# mcu.net
KiCad netlist of a schematic drawn in EAGLE
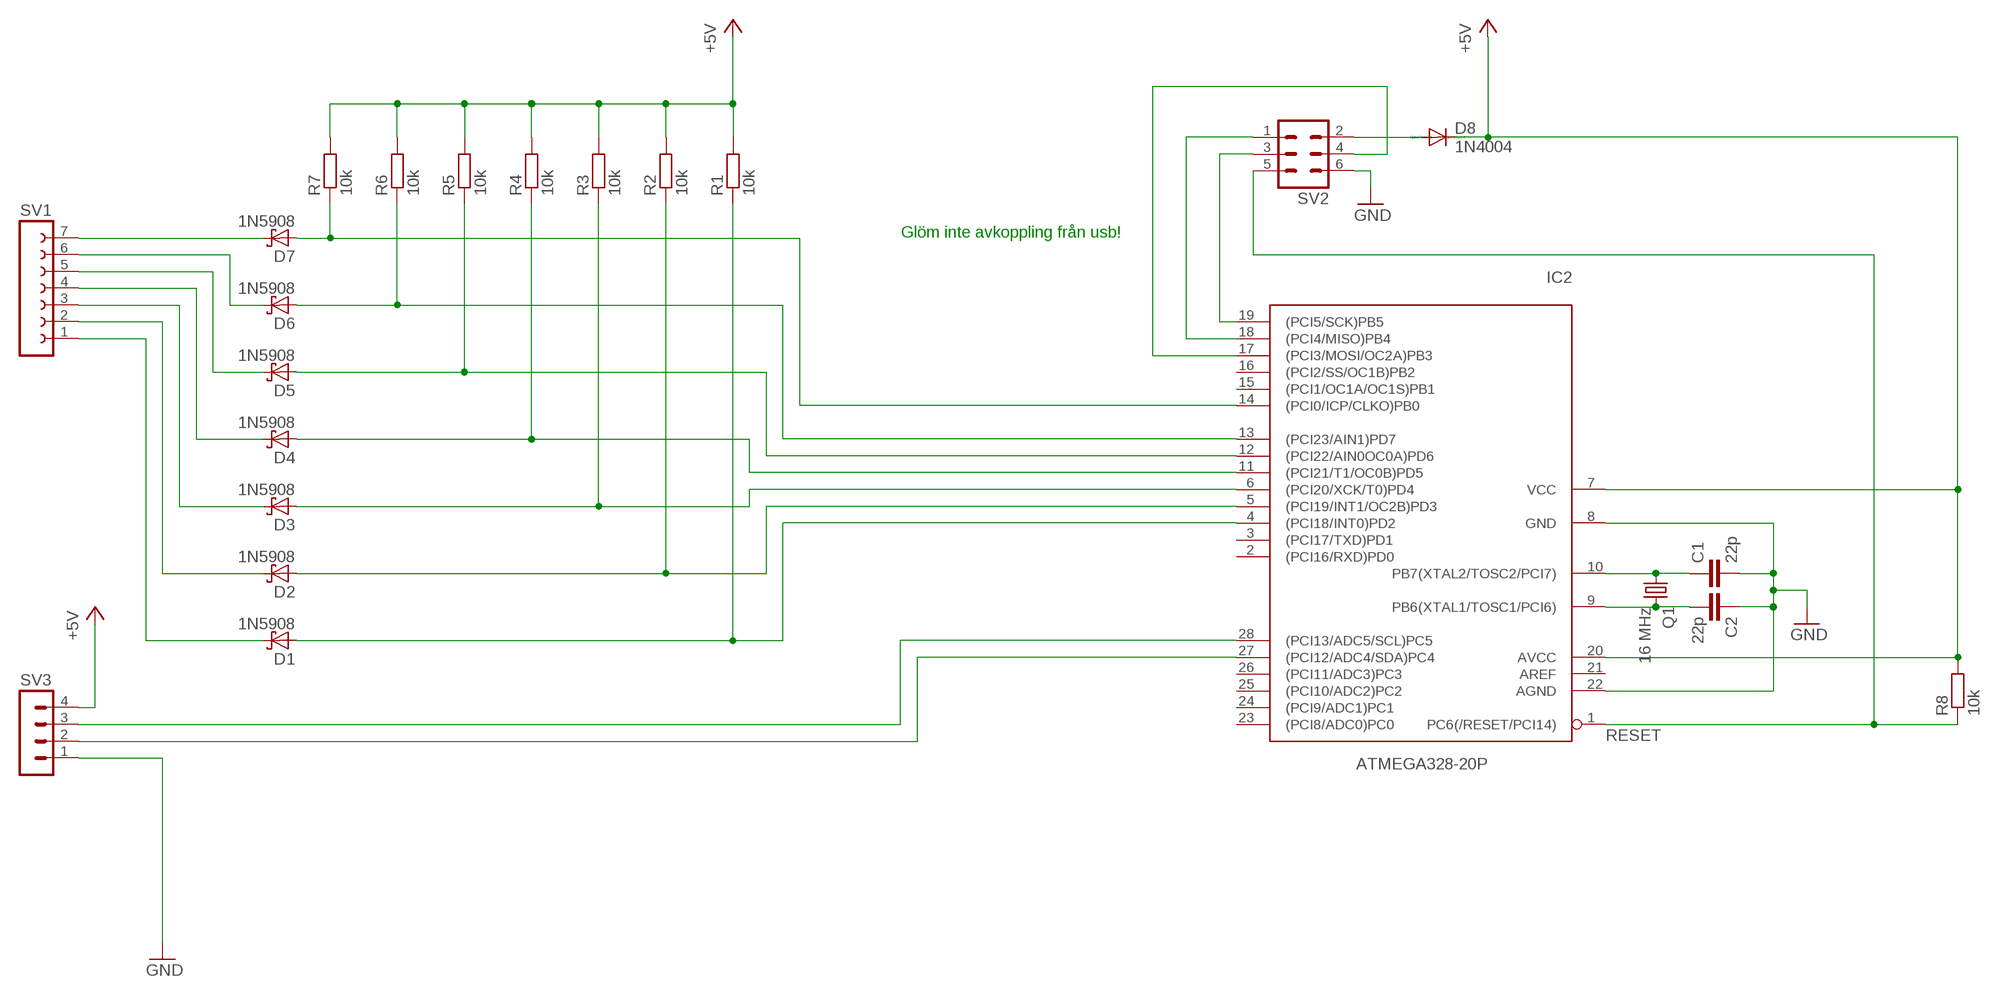
[diagram p0: schematic, sheet 1]

(export (version "E")
  (design (tool "Eeschema 10.0.6"))
  (components
    (comp (ref "C1")
      (value "22p")
      (footprint "eagle-import:C2.5-3")
      (libsource (lib "eagle-import") (part "C2,5-3"))
    )
    (comp (ref "C2")
      (value "22p")
      (footprint "eagle-import:C2.5-3")
      (libsource (lib "eagle-import") (part "C2,5-3"))
    )
    (comp (ref "D1")
      (value "1N5908")
      (footprint "eagle-import:C4111-15")
      (libsource (lib "eagle-import") (part "1N5908"))
    )
    (comp (ref "D2")
      (value "1N5908")
      (footprint "eagle-import:C4111-15")
      (libsource (lib "eagle-import") (part "1N5908"))
    )
    (comp (ref "D3")
      (value "1N5908")
      (footprint "eagle-import:C4111-15")
      (libsource (lib "eagle-import") (part "1N5908"))
    )
    (comp (ref "D4")
      (value "1N5908")
      (footprint "eagle-import:C4111-15")
      (libsource (lib "eagle-import") (part "1N5908"))
    )
    (comp (ref "D5")
      (value "1N5908")
      (footprint "eagle-import:C4111-15")
      (libsource (lib "eagle-import") (part "1N5908"))
    )
    (comp (ref "D6")
      (value "1N5908")
      (footprint "eagle-import:C4111-15")
      (libsource (lib "eagle-import") (part "1N5908"))
    )
    (comp (ref "D7")
      (value "1N5908")
      (footprint "eagle-import:C4111-15")
      (libsource (lib "eagle-import") (part "1N5908"))
    )
    (comp (ref "D8")
      (value "1N4004")
      (footprint "eagle-import:DO41-10")
      (libsource (lib "eagle-import") (part "1N4004"))
    )
    (comp (ref "IC2")
      (value "ATMEGA328-20P")
      (footprint "eagle-import:DIL28-3")
      (libsource (lib "eagle-import") (part "ATMEGA328P-20"))
    )
    (comp (ref "Q1")
      (value "16 MHz")
      (footprint "eagle-import:HC49_S")
      (libsource (lib "eagle-import") (part "CRYSTALHC49S"))
    )
    (comp (ref "R1")
      (value "10k")
      (footprint "eagle-import:0207_10")
      (libsource (lib "eagle-import") (part "R-EU_0207/10"))
    )
    (comp (ref "R2")
      (value "10k")
      (footprint "eagle-import:0207_10")
      (libsource (lib "eagle-import") (part "R-EU_0207/10"))
    )
    (comp (ref "R3")
      (value "10k")
      (footprint "eagle-import:0207_10")
      (libsource (lib "eagle-import") (part "R-EU_0207/10"))
    )
    (comp (ref "R4")
      (value "10k")
      (footprint "eagle-import:0207_10")
      (libsource (lib "eagle-import") (part "R-EU_0207/10"))
    )
    (comp (ref "R5")
      (value "10k")
      (footprint "eagle-import:0207_10")
      (libsource (lib "eagle-import") (part "R-EU_0207/10"))
    )
    (comp (ref "R6")
      (value "10k")
      (footprint "eagle-import:0207_10")
      (libsource (lib "eagle-import") (part "R-EU_0207/10"))
    )
    (comp (ref "R7")
      (value "10k")
      (footprint "eagle-import:0207_10")
      (libsource (lib "eagle-import") (part "R-EU_0207/10"))
    )
    (comp (ref "R8")
      (value "10k")
      (footprint "eagle-import:0207_10")
      (libsource (lib "eagle-import") (part "R-EU_0207/10"))
    )
    (comp (ref "SV1")
      (value "FE07-1")
      (footprint "eagle-import:FE07")
      (libsource (lib "eagle-import") (part "FE07-1"))
    )
    (comp (ref "SV2")
      (value "MA03-2")
      (footprint "eagle-import:MA03-2")
      (libsource (lib "eagle-import") (part "MA03-2"))
    )
    (comp (ref "SV3")
      (value "MA04-1")
      (footprint "eagle-import:MA04-1")
      (libsource (lib "eagle-import") (part "MA04-1"))
    )
  )
  (nets
    (net (code "1") (name "+5V") (class "Default")
      (node (ref "D8") (pin "C") (pinfunction "C_C") (pintype "passive"))
      (node (ref "IC2") (pin "20") (pinfunction "AVCC_20") (pintype "bidirectional"))
      (node (ref "IC2") (pin "7") (pinfunction "VCC_7") (pintype "bidirectional"))
      (node (ref "R1") (pin "2") (pinfunction "2_2") (pintype "passive"))
      (node (ref "R2") (pin "2") (pinfunction "2_2") (pintype "passive"))
      (node (ref "R3") (pin "2") (pinfunction "2_2") (pintype "passive"))
      (node (ref "R4") (pin "2") (pinfunction "2_2") (pintype "passive"))
      (node (ref "R5") (pin "2") (pinfunction "2_2") (pintype "passive"))
      (node (ref "R6") (pin "2") (pinfunction "2_2") (pintype "passive"))
      (node (ref "R7") (pin "2") (pinfunction "2_2") (pintype "passive"))
      (node (ref "R8") (pin "2") (pinfunction "2_2") (pintype "passive"))
      (node (ref "SV3") (pin "4") (pinfunction "4_4") (pintype "passive"))
    )
    (net (code "2") (name "/RESET") (class "Default")
      (node (ref "IC2") (pin "1") (pinfunction "PC6(/RESET/PCI14)_1") (pintype "bidirectional"))
      (node (ref "R8") (pin "1") (pinfunction "1_1") (pintype "passive"))
      (node (ref "SV2") (pin "5") (pinfunction "5_5") (pintype "passive"))
    )
    (net (code "3") (name "GND") (class "Default")
      (node (ref "C1") (pin "2") (pinfunction "2_2") (pintype "passive"))
      (node (ref "C2") (pin "1") (pinfunction "1_1") (pintype "passive"))
      (node (ref "IC2") (pin "22") (pinfunction "AGND_22") (pintype "bidirectional"))
      (node (ref "IC2") (pin "8") (pinfunction "GND_8") (pintype "bidirectional"))
      (node (ref "SV2") (pin "6") (pinfunction "6_6") (pintype "passive"))
      (node (ref "SV3") (pin "1") (pinfunction "1_1") (pintype "passive"))
    )
    (net (code "4") (name "Net-(D1-PadC)") (class "Default")
      (node (ref "D1") (pin "C") (pinfunction "C_C") (pintype "passive"))
      (node (ref "SV1") (pin "1") (pinfunction "1_1") (pintype "passive"))
    )
    (net (code "5") (name "Net-(D2-PadC)") (class "Default")
      (node (ref "D2") (pin "C") (pinfunction "C_C") (pintype "passive"))
      (node (ref "SV1") (pin "2") (pinfunction "2_2") (pintype "passive"))
    )
    (net (code "6") (name "Net-(D3-PadC)") (class "Default")
      (node (ref "D3") (pin "C") (pinfunction "C_C") (pintype "passive"))
      (node (ref "SV1") (pin "3") (pinfunction "3_3") (pintype "passive"))
    )
    (net (code "7") (name "Net-(D4-PadC)") (class "Default")
      (node (ref "D4") (pin "C") (pinfunction "C_C") (pintype "passive"))
      (node (ref "SV1") (pin "4") (pinfunction "4_4") (pintype "passive"))
    )
    (net (code "8") (name "Net-(D5-PadC)") (class "Default")
      (node (ref "D5") (pin "C") (pinfunction "C_C") (pintype "passive"))
      (node (ref "SV1") (pin "5") (pinfunction "5_5") (pintype "passive"))
    )
    (net (code "9") (name "Net-(D6-PadC)") (class "Default")
      (node (ref "D6") (pin "C") (pinfunction "C_C") (pintype "passive"))
      (node (ref "SV1") (pin "6") (pinfunction "6_6") (pintype "passive"))
    )
    (net (code "10") (name "Net-(D7-PadC)") (class "Default")
      (node (ref "D7") (pin "C") (pinfunction "C_C") (pintype "passive"))
      (node (ref "SV1") (pin "7") (pinfunction "7_7") (pintype "passive"))
    )
    (net (code "11") (name "Net-(D8-PadA)") (class "Default")
      (node (ref "D8") (pin "A") (pinfunction "A_A") (pintype "passive"))
      (node (ref "SV2") (pin "2") (pinfunction "2_2") (pintype "passive"))
    )
    (net (code "12") (name "Net-(IC2-(PCI0{slash}ICP{slash}CLKO)PB0)") (class "Default")
      (node (ref "D7") (pin "A") (pinfunction "A_A") (pintype "passive"))
      (node (ref "IC2") (pin "14") (pinfunction "(PCI0/ICP/CLKO)PB0_14") (pintype "bidirectional"))
      (node (ref "R7") (pin "1") (pinfunction "1_1") (pintype "passive"))
    )
    (net (code "13") (name "Net-(IC2-(PCI3{slash}MOSI{slash}OC2A)PB3)") (class "Default")
      (node (ref "IC2") (pin "17") (pinfunction "(PCI3/MOSI/OC2A)PB3_17") (pintype "bidirectional"))
      (node (ref "SV2") (pin "4") (pinfunction "4_4") (pintype "passive"))
    )
    (net (code "14") (name "Net-(IC2-(PCI4{slash}MISO)PB4)") (class "Default")
      (node (ref "IC2") (pin "18") (pinfunction "(PCI4/MISO)PB4_18") (pintype "bidirectional"))
      (node (ref "SV2") (pin "1") (pinfunction "1_1") (pintype "passive"))
    )
    (net (code "15") (name "Net-(IC2-(PCI5{slash}SCK)PB5)") (class "Default")
      (node (ref "IC2") (pin "19") (pinfunction "(PCI5/SCK)PB5_19") (pintype "bidirectional"))
      (node (ref "SV2") (pin "3") (pinfunction "3_3") (pintype "passive"))
    )
    (net (code "16") (name "Net-(IC2-(PCI12{slash}ADC4{slash}SDA)PC4)") (class "Default")
      (node (ref "IC2") (pin "27") (pinfunction "(PCI12/ADC4/SDA)PC4_27") (pintype "bidirectional"))
      (node (ref "SV3") (pin "2") (pinfunction "2_2") (pintype "passive"))
    )
    (net (code "17") (name "Net-(IC2-(PCI13{slash}ADC5{slash}SCL)PC5)") (class "Default")
      (node (ref "IC2") (pin "28") (pinfunction "(PCI13/ADC5/SCL)PC5_28") (pintype "bidirectional"))
      (node (ref "SV3") (pin "3") (pinfunction "3_3") (pintype "passive"))
    )
    (net (code "18") (name "Net-(IC2-(PCI18{slash}INT0)PD2)") (class "Default")
      (node (ref "D1") (pin "A") (pinfunction "A_A") (pintype "passive"))
      (node (ref "IC2") (pin "4") (pinfunction "(PCI18/INT0)PD2_4") (pintype "bidirectional"))
      (node (ref "R1") (pin "1") (pinfunction "1_1") (pintype "passive"))
    )
    (net (code "19") (name "Net-(IC2-(PCI19{slash}INT1{slash}OC2B)PD3)") (class "Default")
      (node (ref "D2") (pin "A") (pinfunction "A_A") (pintype "passive"))
      (node (ref "IC2") (pin "5") (pinfunction "(PCI19/INT1/OC2B)PD3_5") (pintype "bidirectional"))
      (node (ref "R2") (pin "1") (pinfunction "1_1") (pintype "passive"))
    )
    (net (code "20") (name "Net-(IC2-(PCI20{slash}XCK{slash}T0)PD4)") (class "Default")
      (node (ref "D3") (pin "A") (pinfunction "A_A") (pintype "passive"))
      (node (ref "IC2") (pin "6") (pinfunction "(PCI20/XCK/T0)PD4_6") (pintype "bidirectional"))
      (node (ref "R3") (pin "1") (pinfunction "1_1") (pintype "passive"))
    )
    (net (code "21") (name "Net-(IC2-(PCI21{slash}T1{slash}OC0B)PD5)") (class "Default")
      (node (ref "D4") (pin "A") (pinfunction "A_A") (pintype "passive"))
      (node (ref "IC2") (pin "11") (pinfunction "(PCI21/T1/OC0B)PD5_11") (pintype "bidirectional"))
      (node (ref "R4") (pin "1") (pinfunction "1_1") (pintype "passive"))
    )
    (net (code "22") (name "Net-(IC2-(PCI22{slash}AIN0OC0A)PD6)") (class "Default")
      (node (ref "D5") (pin "A") (pinfunction "A_A") (pintype "passive"))
      (node (ref "IC2") (pin "12") (pinfunction "(PCI22/AIN0OC0A)PD6_12") (pintype "bidirectional"))
      (node (ref "R5") (pin "1") (pinfunction "1_1") (pintype "passive"))
    )
    (net (code "23") (name "Net-(IC2-(PCI23{slash}AIN1)PD7)") (class "Default")
      (node (ref "D6") (pin "A") (pinfunction "A_A") (pintype "passive"))
      (node (ref "IC2") (pin "13") (pinfunction "(PCI23/AIN1)PD7_13") (pintype "bidirectional"))
      (node (ref "R6") (pin "1") (pinfunction "1_1") (pintype "passive"))
    )
    (net (code "24") (name "Net-(IC2-PB6(XTAL1{slash}TOSC1{slash}PCI6))") (class "Default")
      (node (ref "C2") (pin "2") (pinfunction "2_2") (pintype "passive"))
      (node (ref "IC2") (pin "9") (pinfunction "PB6(XTAL1/TOSC1/PCI6)_9") (pintype "bidirectional"))
      (node (ref "Q1") (pin "2") (pinfunction "2_2") (pintype "passive"))
    )
    (net (code "25") (name "Net-(IC2-PB7(XTAL2{slash}TOSC2{slash}PCI7))") (class "Default")
      (node (ref "C1") (pin "1") (pinfunction "1_1") (pintype "passive"))
      (node (ref "IC2") (pin "10") (pinfunction "PB7(XTAL2/TOSC2/PCI7)_10") (pintype "bidirectional"))
      (node (ref "Q1") (pin "1") (pinfunction "1_1") (pintype "passive"))
    )
    (net (code "26") (name "unconnected-(IC2-(PCI1{slash}OC1A{slash}OC1S)PB1-Pad15)") (class "Default")
      (node (ref "IC2") (pin "15") (pinfunction "(PCI1/OC1A/OC1S)PB1_15") (pintype "bidirectional"))
    )
    (net (code "27") (name "unconnected-(IC2-(PCI2{slash}SS{slash}OC1B)PB2-Pad16)") (class "Default")
      (node (ref "IC2") (pin "16") (pinfunction "(PCI2/SS/OC1B)PB2_16") (pintype "bidirectional"))
    )
    (net (code "28") (name "unconnected-(IC2-(PCI8{slash}ADC0)PC0-Pad23)") (class "Default")
      (node (ref "IC2") (pin "23") (pinfunction "(PCI8/ADC0)PC0_23") (pintype "bidirectional"))
    )
    (net (code "29") (name "unconnected-(IC2-(PCI9{slash}ADC1)PC1-Pad24)") (class "Default")
      (node (ref "IC2") (pin "24") (pinfunction "(PCI9/ADC1)PC1_24") (pintype "bidirectional"))
    )
    (net (code "30") (name "unconnected-(IC2-(PCI10{slash}ADC2)PC2-Pad25)") (class "Default")
      (node (ref "IC2") (pin "25") (pinfunction "(PCI10/ADC2)PC2_25") (pintype "bidirectional"))
    )
    (net (code "31") (name "unconnected-(IC2-(PCI11{slash}ADC3)PC3-Pad26)") (class "Default")
      (node (ref "IC2") (pin "26") (pinfunction "(PCI11/ADC3)PC3_26") (pintype "bidirectional"))
    )
    (net (code "32") (name "unconnected-(IC2-(PCI16{slash}RXD)PD0-Pad2)") (class "Default")
      (node (ref "IC2") (pin "2") (pinfunction "(PCI16/RXD)PD0_2") (pintype "bidirectional"))
    )
    (net (code "33") (name "unconnected-(IC2-(PCI17{slash}TXD)PD1-Pad3)") (class "Default")
      (node (ref "IC2") (pin "3") (pinfunction "(PCI17/TXD)PD1_3") (pintype "bidirectional"))
    )
    (net (code "34") (name "unconnected-(IC2-AREF-Pad21)") (class "Default")
      (node (ref "IC2") (pin "21") (pinfunction "AREF_21") (pintype "bidirectional"))
    )
  )
)
